# KickerBoard.net
KiCad netlist of a schematic drawn in EAGLE
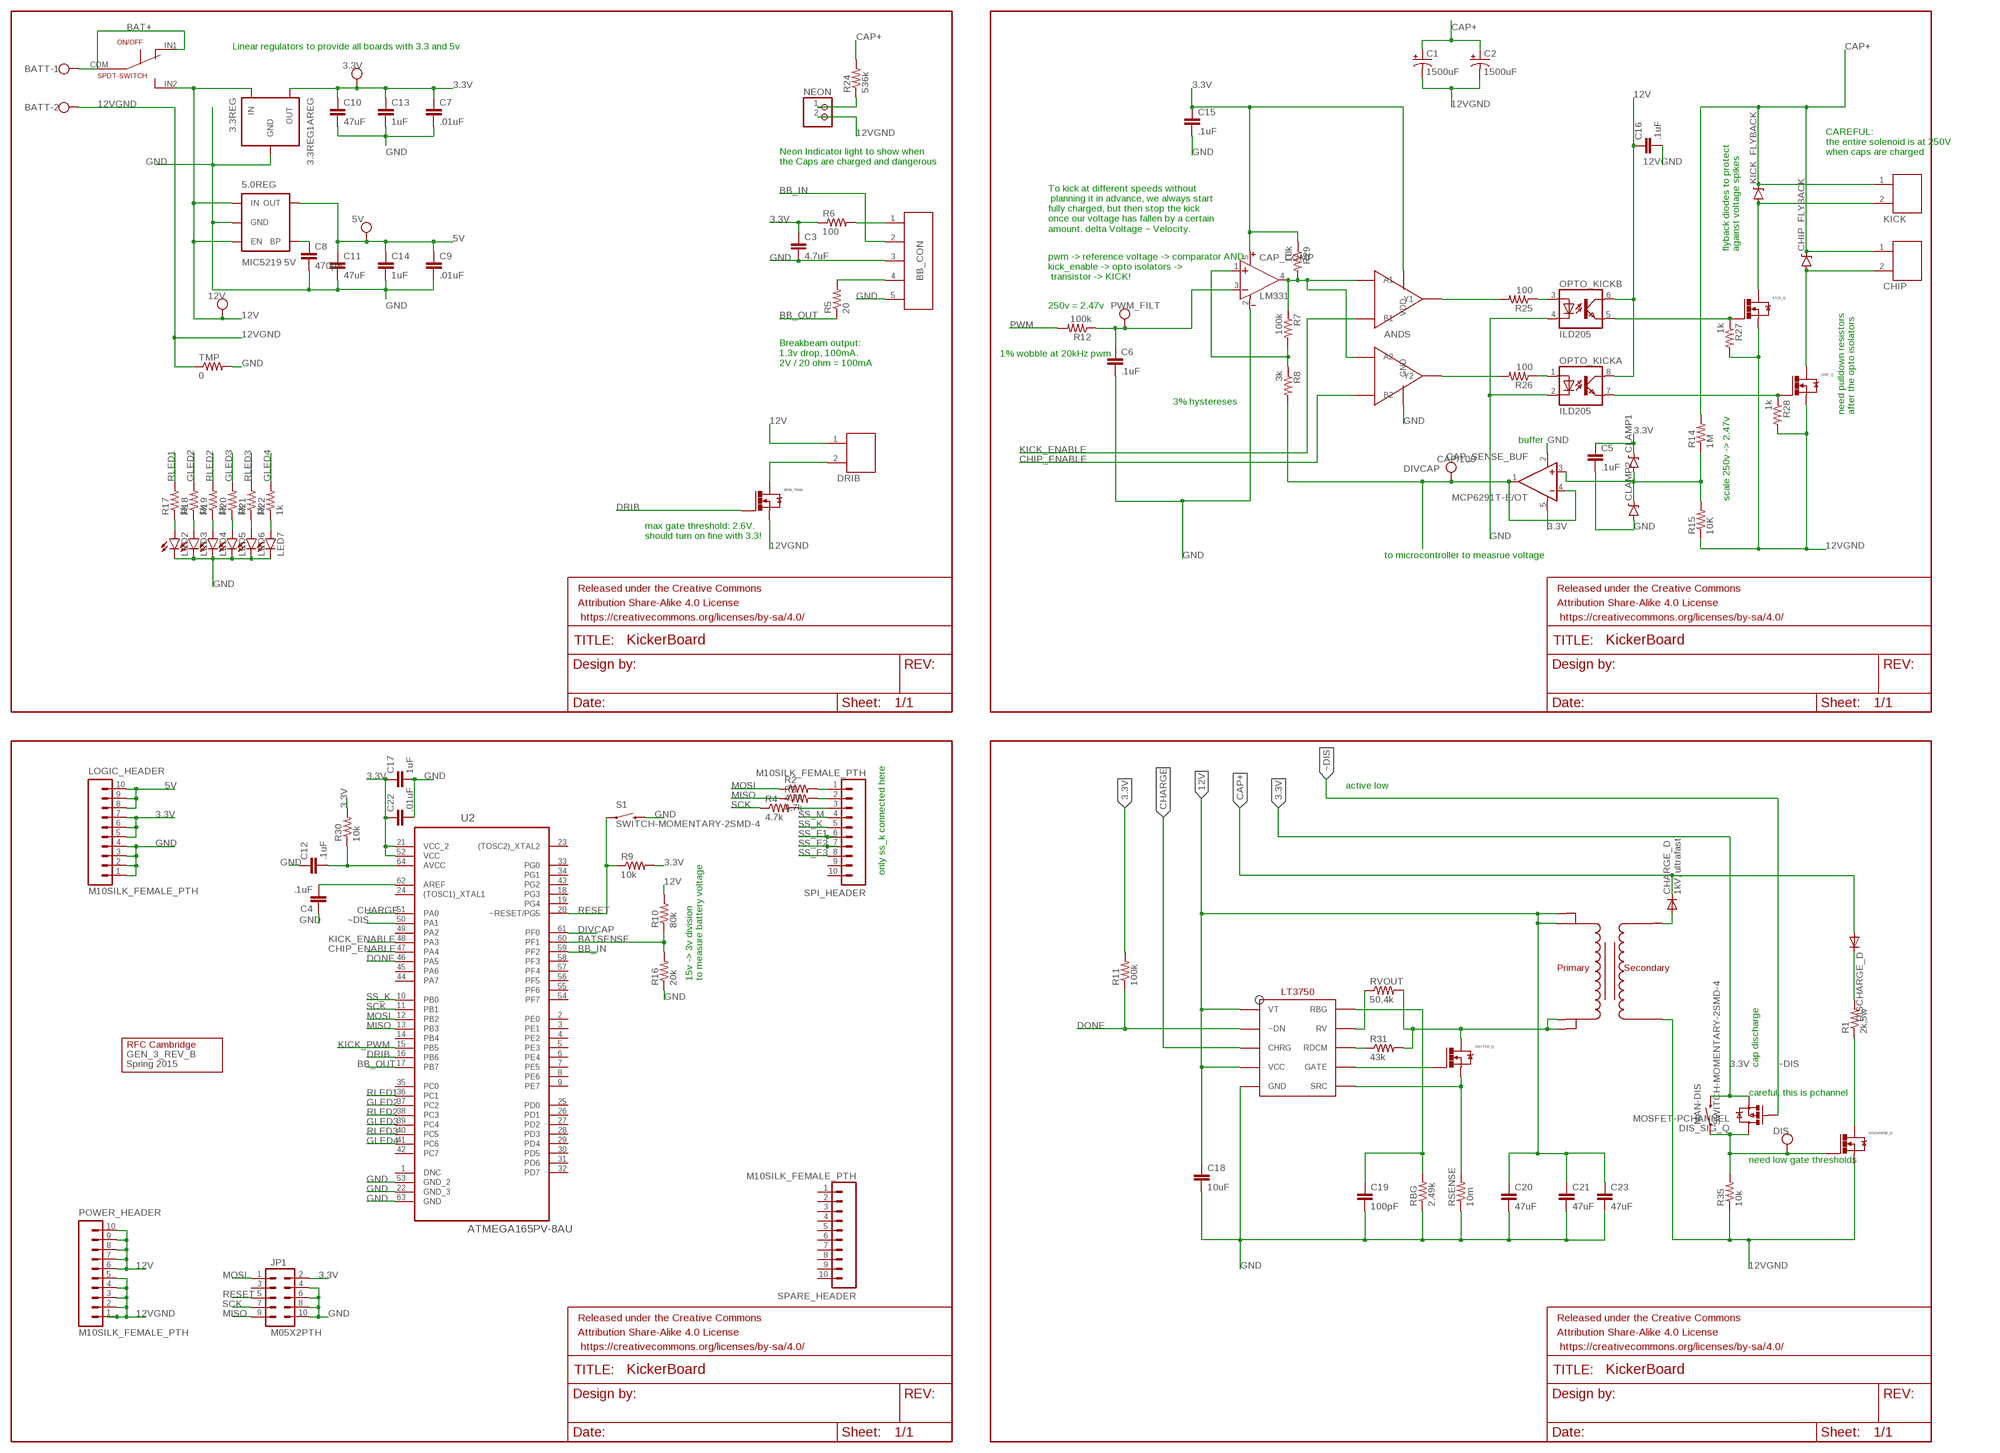
[diagram p0: schematic, sheet 1]

(export (version "E")
  (design (tool "Eeschema 10.0.6"))
  (components
    (comp (ref "3.3REG")
      (value "3.3REG1AREG")
      (footprint "eagle-import:DPAK")
      (libsource (lib "eagle-import") (part "3.3REG1AREG"))
    )
    (comp (ref "3.3V")
      (value "TEST_PT")
      (footprint "eagle-import:TESTING_PT")
      (libsource (lib "eagle-import") (part "TEST_PT"))
    )
    (comp (ref "5.0REG")
      (value "MIC5219 5V")
      (footprint "eagle-import:SOT23-5")
      (libsource (lib "eagle-import") (part "V_REG_MIC52195V"))
    )
    (comp (ref "5V")
      (value "TEST_PT")
      (footprint "eagle-import:TESTING_PT")
      (libsource (lib "eagle-import") (part "TEST_PT"))
    )
    (comp (ref "12V")
      (value "TEST_PT")
      (footprint "eagle-import:TESTING_PT")
      (libsource (lib "eagle-import") (part "TEST_PT"))
    )
    (comp (ref "ANDS")
      (value "AND-DUAL")
      (footprint "eagle-import:TSSOP8")
      (libsource (lib "eagle-import") (part "AND-DUAL"))
    )
    (comp (ref "BATT")
      (value "W237-102")
      (footprint "eagle-import:W237-102")
      (fields (field (name "MPN") "237-102"))
      (libsource (lib "eagle-import") (part "W237-102"))
    )
    (comp (ref "BB_CON")
      (value "JST-5")
      (footprint "eagle-import:JST-5-2MM")
      (libsource (lib "eagle-import") (part "JST-5"))
    )
    (comp (ref "C1")
      (value "1500uF")
      (footprint "eagle-import:EB35D")
      (libsource (lib "eagle-import") (part "CPOL-USE10-35"))
    )
    (comp (ref "C2")
      (value "1500uF")
      (footprint "eagle-import:EB35D")
      (libsource (lib "eagle-import") (part "CPOL-USE10-35"))
    )
    (comp (ref "C3")
      (value "4.7uF")
      (footprint "eagle-import:0805")
      (libsource (lib "eagle-import") (part "CAP0805"))
    )
    (comp (ref "C4")
      (value ".1uF")
      (footprint "eagle-import:0805")
      (libsource (lib "eagle-import") (part "CAP0805"))
    )
    (comp (ref "C5")
      (value ".1uF")
      (footprint "eagle-import:0805")
      (libsource (lib "eagle-import") (part "CAP0805"))
    )
    (comp (ref "C6")
      (value ".1uF")
      (footprint "eagle-import:0805")
      (libsource (lib "eagle-import") (part "CAP0805"))
    )
    (comp (ref "C7")
      (value ".01uF")
      (footprint "eagle-import:0805")
      (libsource (lib "eagle-import") (part "CAP0805"))
    )
    (comp (ref "C8")
      (value "470pF")
      (footprint "eagle-import:0805")
      (libsource (lib "eagle-import") (part "CAP0805"))
    )
    (comp (ref "C9")
      (value ".01uF")
      (footprint "eagle-import:0805")
      (libsource (lib "eagle-import") (part "CAP0805"))
    )
    (comp (ref "C10")
      (value "47uF")
      (footprint "eagle-import:1206")
      (libsource (lib "eagle-import") (part "CAP1206"))
    )
    (comp (ref "C11")
      (value "47uF")
      (footprint "eagle-import:1206")
      (libsource (lib "eagle-import") (part "CAP1206"))
    )
    (comp (ref "C12")
      (value ".1uF")
      (footprint "eagle-import:0805")
      (libsource (lib "eagle-import") (part "CAP0805"))
    )
    (comp (ref "C13")
      (value "1uF")
      (footprint "eagle-import:0805")
      (libsource (lib "eagle-import") (part "CAP0805"))
    )
    (comp (ref "C14")
      (value "1uF")
      (footprint "eagle-import:0805")
      (libsource (lib "eagle-import") (part "CAP0805"))
    )
    (comp (ref "C15")
      (value ".1uF")
      (footprint "eagle-import:0805")
      (libsource (lib "eagle-import") (part "CAP0805"))
    )
    (comp (ref "C16")
      (value ".1uF")
      (footprint "eagle-import:0805")
      (libsource (lib "eagle-import") (part "CAP0805"))
    )
    (comp (ref "C17")
      (value "1uF")
      (footprint "eagle-import:0805")
      (libsource (lib "eagle-import") (part "CAP0805"))
    )
    (comp (ref "C18")
      (value "10uF")
      (footprint "eagle-import:0805")
      (libsource (lib "eagle-import") (part "CAP0805"))
    )
    (comp (ref "C19")
      (value "100pF")
      (footprint "eagle-import:0805")
      (libsource (lib "eagle-import") (part "CAP0805"))
    )
    (comp (ref "C20")
      (value "47uF")
      (footprint "eagle-import:1206")
      (libsource (lib "eagle-import") (part "CAP1206"))
    )
    (comp (ref "C21")
      (value "47uF")
      (footprint "eagle-import:1206")
      (libsource (lib "eagle-import") (part "CAP1206"))
    )
    (comp (ref "C22")
      (value ".01uF")
      (footprint "eagle-import:0805")
      (libsource (lib "eagle-import") (part "CAP0805"))
    )
    (comp (ref "C23")
      (value "47uF")
      (footprint "eagle-import:1206")
      (libsource (lib "eagle-import") (part "CAP1206"))
    )
    (comp (ref "CAP/100")
      (value "TEST_PT")
      (footprint "eagle-import:TESTING_PT")
      (libsource (lib "eagle-import") (part "TEST_PT"))
    )
    (comp (ref "CAP_COMP")
      (value "LM331")
      (footprint "eagle-import:SOT23-5")
      (libsource (lib "eagle-import") (part "LM331"))
    )
    (comp (ref "CAP_SENSE_BUF")
      (value "MCP6291T-E/OT")
      (footprint "eagle-import:SOT23-5")
      (libsource (lib "eagle-import") (part "MCP6291T-E/OT"))
    )
    (comp (ref "CHARGE_D")
      (value "1kV, ultrafast")
      (footprint "eagle-import:DO214AC")
      (libsource (lib "eagle-import") (part "DIODE-DO214AC"))
    )
    (comp (ref "CHARGE_U")
      (value "LT3750")
      (footprint "eagle-import:10-MSOP")
      (libsource (lib "eagle-import") (part "LT3750"))
    )
    (comp (ref "CHIP")
      (value "JST-22MM")
      (footprint "eagle-import:JST-2-2MM")
      (libsource (lib "eagle-import") (part "JST-22MM"))
    )
    (comp (ref "CHIP_FLYBACK")
      (value "DIODE-ZENERDO214AB")
      (footprint "eagle-import:DO214AB")
      (libsource (lib "eagle-import") (part "DIODE-ZENERDO214AB"))
    )
    (comp (ref "CHIP_Q")
      (value "N-MOSFETDPAK")
      (footprint "eagle-import:DPAK")
      (libsource (lib "eagle-import") (part "N-MOSFETDPAK"))
    )
    (comp (ref "CLAMP1")
      (value "DIODE-ZENERDO214AC")
      (footprint "eagle-import:DO214AC")
      (libsource (lib "eagle-import") (part "DIODE-ZENERDO214AC"))
    )
    (comp (ref "CLAMP2")
      (value "DIODE-ZENERDO214AC")
      (footprint "eagle-import:DO214AC")
      (libsource (lib "eagle-import") (part "DIODE-ZENERDO214AC"))
    )
    (comp (ref "DIS")
      (value "TEST_PT")
      (footprint "eagle-import:TESTING_PT")
      (libsource (lib "eagle-import") (part "TEST_PT"))
    )
    (comp (ref "DISCHARGE_D")
      (value "DIODE-DO214AA")
      (footprint "eagle-import:DO214AA")
      (libsource (lib "eagle-import") (part "DIODE-DO214AA"))
    )
    (comp (ref "DISCHARGE_Q")
      (value "N-MOSFETDPAK")
      (footprint "eagle-import:DPAK")
      (libsource (lib "eagle-import") (part "N-MOSFETDPAK"))
    )
    (comp (ref "DIS_SIG_Q")
      (value "MOSFET-PCHANNEL")
      (footprint "eagle-import:SOT23-3")
      (libsource (lib "eagle-import") (part "MOSFET-PCHANNEL"))
    )
    (comp (ref "DRIB")
      (value "JST-22MM")
      (footprint "eagle-import:JST-2-2MM")
      (libsource (lib "eagle-import") (part "JST-22MM"))
    )
    (comp (ref "DRIB_TRAN")
      (value "N-MOSFETDPAK")
      (footprint "eagle-import:DPAK")
      (libsource (lib "eagle-import") (part "N-MOSFETDPAK"))
    )
    (comp (ref "FRAME1")
      (value "FRAME-LETTER")
      (footprint "eagle-import:CREATIVE_COMMONS")
      (libsource (lib "eagle-import") (part "FRAME-LETTER"))
    )
    (comp (ref "FRAME2")
      (value "FRAME-LETTER")
      (footprint "eagle-import:CREATIVE_COMMONS")
      (libsource (lib "eagle-import") (part "FRAME-LETTER"))
    )
    (comp (ref "FRAME3")
      (value "FRAME-LETTER")
      (footprint "eagle-import:CREATIVE_COMMONS")
      (libsource (lib "eagle-import") (part "FRAME-LETTER"))
    )
    (comp (ref "FRAME4")
      (value "FRAME-LETTER")
      (footprint "eagle-import:CREATIVE_COMMONS")
      (libsource (lib "eagle-import") (part "FRAME-LETTER"))
    )
    (comp (ref "GEN_3_REV_B")
      (value "Spring 2015")
      (footprint "eagle-import:LOGO")
      (libsource (lib "eagle-import") (part "LOGO"))
    )
    (comp (ref "JP1")
      (value "M05X2PTH")
      (footprint "eagle-import:AVR_ICSP")
      (libsource (lib "eagle-import") (part "M05X2PTH"))
    )
    (comp (ref "KICK")
      (value "JST-22MM")
      (footprint "eagle-import:JST-2-2MM")
      (libsource (lib "eagle-import") (part "JST-22MM"))
    )
    (comp (ref "KICK_FLYBACK")
      (value "DIODE-ZENERDO214AB")
      (footprint "eagle-import:DO214AB")
      (libsource (lib "eagle-import") (part "DIODE-ZENERDO214AB"))
    )
    (comp (ref "KICK_Q")
      (value "N-MOSFETDPAK")
      (footprint "eagle-import:DPAK")
      (libsource (lib "eagle-import") (part "N-MOSFETDPAK"))
    )
    (comp (ref "LED2")
      (value "LED1206")
      (footprint "eagle-import:LED-1206")
      (libsource (lib "eagle-import") (part "LED1206"))
    )
    (comp (ref "LED3")
      (value "LED1206")
      (footprint "eagle-import:LED-1206")
      (libsource (lib "eagle-import") (part "LED1206"))
    )
    (comp (ref "LED4")
      (value "LED1206")
      (footprint "eagle-import:LED-1206")
      (libsource (lib "eagle-import") (part "LED1206"))
    )
    (comp (ref "LED5")
      (value "LED1206")
      (footprint "eagle-import:LED-1206")
      (libsource (lib "eagle-import") (part "LED1206"))
    )
    (comp (ref "LED6")
      (value "LED1206")
      (footprint "eagle-import:LED-1206")
      (libsource (lib "eagle-import") (part "LED1206"))
    )
    (comp (ref "LED7")
      (value "LED1206")
      (footprint "eagle-import:LED-1206")
      (libsource (lib "eagle-import") (part "LED1206"))
    )
    (comp (ref "LOGIC_HEADER")
      (value "M10SILK_FEMALE_PTH")
      (footprint "eagle-import:1X10")
      (libsource (lib "eagle-import") (part "M10SILK_FEMALE_PTH"))
    )
    (comp (ref "MAN-DIS")
      (value "SWITCH-MOMENTARY-2SMD-4")
      (footprint "eagle-import:TACTILE_SWITCH_TALL")
      (libsource (lib "eagle-import") (part "SWITCH-MOMENTARY-2SMD-4"))
    )
    (comp (ref "NEON")
      (value "PINHD-1X2")
      (footprint "eagle-import:1X02")
      (libsource (lib "eagle-import") (part "PINHD-1X2"))
    )
    (comp (ref "ON/OFF")
      (value "SPDT-SWITCH")
      (footprint "eagle-import:CK_SWITCH")
      (libsource (lib "eagle-import") (part "SPDT-SWITCH"))
    )
    (comp (ref "OPTO_KICK")
      (value "ILD205")
      (footprint "eagle-import:SOIC08")
      (fields (field (name "MF") "VISHAY/TELEFUNKEN") (field (name "MPN") "ILD205T"))
      (libsource (lib "eagle-import") (part "ILD205"))
    )
    (comp (ref "POWER_HEADER")
      (value "M10SILK_FEMALE_PTH")
      (footprint "eagle-import:1X10")
      (libsource (lib "eagle-import") (part "M10SILK_FEMALE_PTH"))
    )
    (comp (ref "PWM_FILT")
      (value "TEST_PT")
      (footprint "eagle-import:TESTING_PT")
      (libsource (lib "eagle-import") (part "TEST_PT"))
    )
    (comp (ref "R1")
      (value "2k,5w")
      (footprint "eagle-import:5WRESISTOR")
      (libsource (lib "eagle-import") (part "RESISTOR"))
    )
    (comp (ref "R2")
      (value "4.7k")
      (footprint "eagle-import:0805")
      (libsource (lib "eagle-import") (part "RESISTOR0805-RES"))
    )
    (comp (ref "R3")
      (value "4.7k")
      (footprint "eagle-import:0805")
      (libsource (lib "eagle-import") (part "RESISTOR0805-RES"))
    )
    (comp (ref "R4")
      (value "4.7k")
      (footprint "eagle-import:0805")
      (libsource (lib "eagle-import") (part "RESISTOR0805-RES"))
    )
    (comp (ref "R5")
      (value "20")
      (footprint "eagle-import:0805")
      (libsource (lib "eagle-import") (part "RESISTOR0805-RES"))
    )
    (comp (ref "R6")
      (value "100")
      (footprint "eagle-import:0805")
      (libsource (lib "eagle-import") (part "RESISTOR0805-RES"))
    )
    (comp (ref "R7")
      (value "100k")
      (footprint "eagle-import:0805")
      (libsource (lib "eagle-import") (part "RESISTOR0805-RES"))
    )
    (comp (ref "R8")
      (value "3k")
      (footprint "eagle-import:0805")
      (libsource (lib "eagle-import") (part "RESISTOR0805-RES"))
    )
    (comp (ref "R9")
      (value "10k")
      (footprint "eagle-import:0805")
      (libsource (lib "eagle-import") (part "RESISTOR0805-RES"))
    )
    (comp (ref "R10")
      (value "80k")
      (footprint "eagle-import:0805")
      (libsource (lib "eagle-import") (part "RESISTOR0805-RES"))
    )
    (comp (ref "R11")
      (value "100k")
      (footprint "eagle-import:0805")
      (libsource (lib "eagle-import") (part "RESISTOR0805-RES"))
    )
    (comp (ref "R12")
      (value "100k")
      (footprint "eagle-import:0805")
      (libsource (lib "eagle-import") (part "RESISTOR0805-RES"))
    )
    (comp (ref "R14")
      (value "1M")
      (footprint "eagle-import:0805")
      (libsource (lib "eagle-import") (part "SparkFun-Resistors_RESISTOR0805-RES"))
    )
    (comp (ref "R15")
      (value "10K")
      (footprint "eagle-import:0805")
      (libsource (lib "eagle-import") (part "SparkFun-Resistors_RESISTOR0805-RES"))
    )
    (comp (ref "R16")
      (value "20k")
      (footprint "eagle-import:0805")
      (libsource (lib "eagle-import") (part "RESISTOR0805-RES"))
    )
    (comp (ref "R17")
      (value "1k")
      (footprint "eagle-import:0805")
      (libsource (lib "eagle-import") (part "RESISTOR0805-RES"))
    )
    (comp (ref "R18")
      (value "1k")
      (footprint "eagle-import:0805")
      (libsource (lib "eagle-import") (part "RESISTOR0805-RES"))
    )
    (comp (ref "R19")
      (value "1k")
      (footprint "eagle-import:0805")
      (libsource (lib "eagle-import") (part "RESISTOR0805-RES"))
    )
    (comp (ref "R20")
      (value "1k")
      (footprint "eagle-import:0805")
      (libsource (lib "eagle-import") (part "RESISTOR0805-RES"))
    )
    (comp (ref "R21")
      (value "1k")
      (footprint "eagle-import:0805")
      (libsource (lib "eagle-import") (part "RESISTOR0805-RES"))
    )
    (comp (ref "R22")
      (value "1k")
      (footprint "eagle-import:0805")
      (libsource (lib "eagle-import") (part "RESISTOR0805-RES"))
    )
    (comp (ref "R24")
      (value "536k")
      (footprint "eagle-import:0805")
      (libsource (lib "eagle-import") (part "RESISTOR0805-RES"))
    )
    (comp (ref "R25")
      (value "100")
      (footprint "eagle-import:0805")
      (libsource (lib "eagle-import") (part "RESISTOR0805-RES"))
    )
    (comp (ref "R26")
      (value "100")
      (footprint "eagle-import:0805")
      (libsource (lib "eagle-import") (part "RESISTOR0805-RES"))
    )
    (comp (ref "R27")
      (value "1k")
      (footprint "eagle-import:0805")
      (libsource (lib "eagle-import") (part "RESISTOR0805-RES"))
    )
    (comp (ref "R28")
      (value "1k")
      (footprint "eagle-import:0805")
      (libsource (lib "eagle-import") (part "RESISTOR0805-RES"))
    )
    (comp (ref "R29")
      (value "10k")
      (footprint "eagle-import:0805")
      (libsource (lib "eagle-import") (part "RESISTOR0805-RES"))
    )
    (comp (ref "R30")
      (value "10k")
      (footprint "eagle-import:0805")
      (libsource (lib "eagle-import") (part "RESISTOR0805-RES"))
    )
    (comp (ref "R31")
      (value "43k")
      (footprint "eagle-import:0805")
      (libsource (lib "eagle-import") (part "RESISTOR0805-RES"))
    )
    (comp (ref "R35")
      (value "10k")
      (footprint "eagle-import:0805")
      (libsource (lib "eagle-import") (part "RESISTOR0805-RES"))
    )
    (comp (ref "RBG")
      (value "2.49k")
      (footprint "eagle-import:0805")
      (libsource (lib "eagle-import") (part "RESISTOR0805-RES"))
    )
    (comp (ref "RSENSE")
      (value "10m")
      (footprint "eagle-import:R2512")
      (libsource (lib "eagle-import") (part "RESISTOR2512"))
    )
    (comp (ref "RVOUT")
      (value "50.4k")
      (footprint "eagle-import:0805")
      (libsource (lib "eagle-import") (part "RESISTOR0805-RES"))
    )
    (comp (ref "S1")
      (value "SWITCH-MOMENTARY-2SMD-4")
      (footprint "eagle-import:TACTILE_SWITCH_TALL")
      (libsource (lib "eagle-import") (part "SWITCH-MOMENTARY-2SMD-4"))
    )
    (comp (ref "SPARE_HEADER")
      (value "M10SILK_FEMALE_PTH")
      (footprint "eagle-import:1X10")
      (libsource (lib "eagle-import") (part "M10SILK_FEMALE_PTH"))
    )
    (comp (ref "SPI_HEADER")
      (value "M10SILK_FEMALE_PTH")
      (footprint "eagle-import:1X10")
      (libsource (lib "eagle-import") (part "M10SILK_FEMALE_PTH"))
    )
    (comp (ref "SWITCH_Q")
      (value "N-MOSFETDPAK")
      (footprint "eagle-import:DPAK")
      (libsource (lib "eagle-import") (part "N-MOSFETDPAK"))
    )
    (comp (ref "TMP")
      (value "0")
      (footprint "eagle-import:0805")
      (libsource (lib "eagle-import") (part "RESISTOR0805-RES"))
    )
    (comp (ref "U$1")
      (value "32052-TRANSFORMER")
      (footprint "eagle-import:10-TRANSFORMER")
      (libsource (lib "eagle-import") (part "32052-TRANSFORMER"))
    )
    (comp (ref "U2")
      (value "ATMEGA165PV-8AU")
      (footprint "eagle-import:QFP80P1600X1600X120-64N")
      (libsource (lib "eagle-import") (part "ATMEGA165PV-8AU"))
    )
  )
  (nets
    (net (code "1") (name "/5V") (class "Default")
      (node (ref "5.0REG") (pin "5") (pinfunction "OUT_5") (pintype "passive"))
      (node (ref "5V") (pin "P$1") (pinfunction "P$1_P$1") (pintype "bidirectional"))
      (node (ref "C11") (pin "1") (pinfunction "1_1") (pintype "passive"))
      (node (ref "C14") (pin "1") (pinfunction "1_1") (pintype "passive"))
      (node (ref "C9") (pin "1") (pinfunction "1_1") (pintype "passive"))
      (node (ref "LOGIC_HEADER") (pin "10") (pinfunction "10_10") (pintype "passive"))
      (node (ref "LOGIC_HEADER") (pin "8") (pinfunction "8_8") (pintype "passive"))
      (node (ref "LOGIC_HEADER") (pin "9") (pinfunction "9_9") (pintype "passive"))
    )
    (net (code "2") (name "/12VGND") (class "Default")
      (node (ref "BATT") (pin "2") (pinfunction "KL_2") (pintype "passive"))
      (node (ref "C1") (pin "-") (pinfunction "-_-") (pintype "passive"))
      (node (ref "C16") (pin "2") (pinfunction "2_2") (pintype "passive"))
      (node (ref "C2") (pin "-") (pinfunction "-_-") (pintype "passive"))
      (node (ref "CHIP_Q") (pin "SOURCE") (pinfunction "S_SOURCE") (pintype "bidirectional"))
      (node (ref "DISCHARGE_Q") (pin "SOURCE") (pinfunction "S_SOURCE") (pintype "bidirectional"))
      (node (ref "DRIB_TRAN") (pin "SOURCE") (pinfunction "S_SOURCE") (pintype "bidirectional"))
      (node (ref "KICK_Q") (pin "SOURCE") (pinfunction "S_SOURCE") (pintype "bidirectional"))
      (node (ref "NEON") (pin "2") (pinfunction "2_2") (pintype "passive"))
      (node (ref "POWER_HEADER") (pin "1") (pinfunction "1_1") (pintype "passive"))
      (node (ref "POWER_HEADER") (pin "2") (pinfunction "2_2") (pintype "passive"))
      (node (ref "POWER_HEADER") (pin "3") (pinfunction "3_3") (pintype "passive"))
      (node (ref "POWER_HEADER") (pin "4") (pinfunction "4_4") (pintype "passive"))
      (node (ref "POWER_HEADER") (pin "5") (pinfunction "5_5") (pintype "passive"))
      (node (ref "R15") (pin "1") (pinfunction "1_1") (pintype "passive"))
      (node (ref "R27") (pin "2") (pinfunction "2_2") (pintype "passive"))
      (node (ref "R28") (pin "2") (pinfunction "2_2") (pintype "passive"))
      (node (ref "R35") (pin "1") (pinfunction "1_1") (pintype "passive"))
      (node (ref "TMP") (pin "1") (pinfunction "1_1") (pintype "passive"))
      (node (ref "U$1") (pin "P$10") (pinfunction "P$10_P$10") (pintype "bidirectional"))
    )
    (net (code "3") (name "/BAT+") (class "Default")
      (node (ref "BATT") (pin "1") (pinfunction "KL_1") (pintype "passive"))
      (node (ref "ON/OFF") (pin "COM") (pinfunction "COM_COM") (pintype "bidirectional"))
      (node (ref "ON/OFF") (pin "IN1") (pinfunction "P1_IN1") (pintype "bidirectional"))
    )
    (net (code "4") (name "/BATSENSE") (class "Default")
      (node (ref "R10") (pin "1") (pinfunction "1_1") (pintype "passive"))
      (node (ref "R16") (pin "2") (pinfunction "2_2") (pintype "passive"))
      (node (ref "U2") (pin "60") (pinfunction "PF1_60") (pintype "bidirectional"))
    )
    (net (code "5") (name "/BB_IN") (class "Default")
      (node (ref "BB_CON") (pin "2") (pinfunction "P$2_2") (pintype "bidirectional"))
      (node (ref "U2") (pin "59") (pinfunction "PF2_59") (pintype "bidirectional"))
    )
    (net (code "6") (name "/BB_OUT") (class "Default")
      (node (ref "R5") (pin "1") (pinfunction "1_1") (pintype "passive"))
      (node (ref "U2") (pin "17") (pinfunction "PB7_17") (pintype "bidirectional"))
    )
    (net (code "7") (name "/CHIP_ENABLE") (class "Default")
      (node (ref "ANDS") (pin "P$6") (pinfunction "B2_P$6") (pintype "bidirectional"))
      (node (ref "U2") (pin "47") (pinfunction "PA4_47") (pintype "bidirectional"))
    )
    (net (code "8") (name "/DIVCAP") (class "Default")
      (node (ref "CAP/100") (pin "P$1") (pinfunction "P$1_P$1") (pintype "bidirectional"))
      (node (ref "CAP_SENSE_BUF") (pin "1") (pinfunction "OUT_1") (pintype "output"))
      (node (ref "CAP_SENSE_BUF") (pin "4") (pinfunction "-IN_4") (pintype "input"))
      (node (ref "R8") (pin "2") (pinfunction "2_2") (pintype "passive"))
      (node (ref "U2") (pin "61") (pinfunction "PF0_61") (pintype "bidirectional"))
    )
    (net (code "9") (name "/DONE") (class "Default")
      (node (ref "CHARGE_U") (pin "P$2") (pinfunction "~{DN}_P$2") (pintype "bidirectional"))
      (node (ref "R11") (pin "1") (pinfunction "1_1") (pintype "passive"))
      (node (ref "U2") (pin "46") (pinfunction "PA5_46") (pintype "bidirectional"))
    )
    (net (code "10") (name "/DRIB") (class "Default")
      (node (ref "DRIB_TRAN") (pin "GATE") (pinfunction "G_GATE") (pintype "bidirectional"))
      (node (ref "U2") (pin "16") (pinfunction "PB6_16") (pintype "bidirectional"))
    )
    (net (code "11") (name "/GLED2") (class "Default")
      (node (ref "R18") (pin "2") (pinfunction "2_2") (pintype "passive"))
      (node (ref "U2") (pin "37") (pinfunction "PC2_37") (pintype "bidirectional"))
    )
    (net (code "12") (name "/GLED3") (class "Default")
      (node (ref "R20") (pin "2") (pinfunction "2_2") (pintype "passive"))
      (node (ref "U2") (pin "39") (pinfunction "PC4_39") (pintype "bidirectional"))
    )
    (net (code "13") (name "/GLED4") (class "Default")
      (node (ref "R22") (pin "2") (pinfunction "2_2") (pintype "passive"))
      (node (ref "U2") (pin "41") (pinfunction "PC6_41") (pintype "bidirectional"))
    )
    (net (code "14") (name "/GND") (class "Default")
      (node (ref "3.3REG") (pin "DRAIN") (pinfunction "GND_DRAIN") (pintype "bidirectional"))
      (node (ref "5.0REG") (pin "2") (pinfunction "GND_2") (pintype "input"))
      (node (ref "ANDS") (pin "P$4") (pinfunction "GND_P$4") (pintype "bidirectional"))
      (node (ref "BB_CON") (pin "3") (pinfunction "P$3_3") (pintype "bidirectional"))
      (node (ref "BB_CON") (pin "5") (pinfunction "P$5_5") (pintype "bidirectional"))
      (node (ref "C10") (pin "2") (pinfunction "2_2") (pintype "passive"))
      (node (ref "C11") (pin "2") (pinfunction "2_2") (pintype "passive"))
      (node (ref "C12") (pin "1") (pinfunction "1_1") (pintype "passive"))
      (node (ref "C13") (pin "2") (pinfunction "2_2") (pintype "passive"))
      (node (ref "C14") (pin "2") (pinfunction "2_2") (pintype "passive"))
      (node (ref "C15") (pin "2") (pinfunction "2_2") (pintype "passive"))
      (node (ref "C17") (pin "2") (pinfunction "2_2") (pintype "passive"))
      (node (ref "C18") (pin "2") (pinfunction "2_2") (pintype "passive"))
      (node (ref "C19") (pin "2") (pinfunction "2_2") (pintype "passive"))
      (node (ref "C20") (pin "2") (pinfunction "2_2") (pintype "passive"))
      (node (ref "C21") (pin "2") (pinfunction "2_2") (pintype "passive"))
      (node (ref "C22") (pin "2") (pinfunction "2_2") (pintype "passive"))
      (node (ref "C23") (pin "2") (pinfunction "2_2") (pintype "passive"))
      (node (ref "C3") (pin "2") (pinfunction "2_2") (pintype "passive"))
      (node (ref "C4") (pin "1") (pinfunction "1_1") (pintype "passive"))
      (node (ref "C5") (pin "2") (pinfunction "2_2") (pintype "passive"))
      (node (ref "C6") (pin "2") (pinfunction "2_2") (pintype "passive"))
      (node (ref "C7") (pin "2") (pinfunction "2_2") (pintype "passive"))
      (node (ref "C8") (pin "2") (pinfunction "2_2") (pintype "passive"))
      (node (ref "C9") (pin "2") (pinfunction "2_2") (pintype "passive"))
      (node (ref "CAP_COMP") (pin "2") (pinfunction "V-_2") (pintype "power_in"))
      (node (ref "CAP_SENSE_BUF") (pin "2") (pinfunction "V-_2") (pintype "power_in"))
      (node (ref "CHARGE_U") (pin "P$5") (pinfunction "GND_P$5") (pintype "bidirectional"))
      (node (ref "CLAMP2") (pin "A") (pinfunction "A_A") (pintype "passive"))
      (node (ref "JP1") (pin "10") (pinfunction "10_10") (pintype "passive"))
      (node (ref "JP1") (pin "4") (pinfunction "4_4") (pintype "passive"))
      (node (ref "JP1") (pin "6") (pinfunction "6_6") (pintype "passive"))
      (node (ref "JP1") (pin "8") (pinfunction "8_8") (pintype "passive"))
      (node (ref "LED2") (pin "C") (pinfunction "C_C") (pintype "passive"))
      (node (ref "LED3") (pin "C") (pinfunction "C_C") (pintype "passive"))
      (node (ref "LED4") (pin "C") (pinfunction "C_C") (pintype "passive"))
      (node (ref "LED5") (pin "C") (pinfunction "C_C") (pintype "passive"))
      (node (ref "LED6") (pin "C") (pinfunction "C_C") (pintype "passive"))
      (node (ref "LED7") (pin "C") (pinfunction "C_C") (pintype "passive"))
      (node (ref "LOGIC_HEADER") (pin "1") (pinfunction "1_1") (pintype "passive"))
      (node (ref "LOGIC_HEADER") (pin "2") (pinfunction "2_2") (pintype "passive"))
      (node (ref "LOGIC_HEADER") (pin "3") (pinfunction "3_3") (pintype "passive"))
      (node (ref "LOGIC_HEADER") (pin "4") (pinfunction "4_4") (pintype "passive"))
      (node (ref "OPTO_KICK") (pin "2") (pinfunction "C_2") (pintype "passive"))
      (node (ref "OPTO_KICK") (pin "4") (pinfunction "C_4") (pintype "passive"))
      (node (ref "R16") (pin "1") (pinfunction "1_1") (pintype "passive"))
      (node (ref "RBG") (pin "1") (pinfunction "1_1") (pintype "passive"))
      (node (ref "RSENSE") (pin "1") (pinfunction "1_1") (pintype "passive"))
      (node (ref "S1") (pin "B2") (pinfunction "2_B2") (pintype "passive"))
      (node (ref "TMP") (pin "2") (pinfunction "2_2") (pintype "passive"))
      (node (ref "U2") (pin "22") (pinfunction "GND_3_22") (pintype "passive"))
      (node (ref "U2") (pin "53") (pinfunction "GND_2_53") (pintype "passive"))
      (node (ref "U2") (pin "63") (pinfunction "GND_63") (pintype "passive"))
    )
    (net (code "15") (name "/KICK_ENABLE") (class "Default")
      (node (ref "ANDS") (pin "P$2") (pinfunction "B1_P$2") (pintype "bidirectional"))
      (node (ref "U2") (pin "48") (pinfunction "PA3_48") (pintype "bidirectional"))
    )
    (net (code "16") (name "/KICK_PWM") (class "Default")
      (node (ref "U2") (pin "15") (pinfunction "PB5_15") (pintype "bidirectional"))
    )
    (net (code "17") (name "/MISO") (class "Default")
      (node (ref "JP1") (pin "9") (pinfunction "9_9") (pintype "passive"))
      (node (ref "R3") (pin "1") (pinfunction "1_1") (pintype "passive"))
      (node (ref "U2") (pin "13") (pinfunction "PB3_13") (pintype "bidirectional"))
    )
    (net (code "18") (name "/MOSI") (class "Default")
      (node (ref "JP1") (pin "1") (pinfunction "1_1") (pintype "passive"))
      (node (ref "R2") (pin "1") (pinfunction "1_1") (pintype "passive"))
      (node (ref "U2") (pin "12") (pinfunction "PB2_12") (pintype "bidirectional"))
    )
    (net (code "19") (name "/PWM") (class "Default")
      (node (ref "R12") (pin "2") (pinfunction "2_2") (pintype "passive"))
    )
    (net (code "20") (name "/RESET") (class "Default")
      (node (ref "JP1") (pin "5") (pinfunction "5_5") (pintype "passive"))
      (node (ref "R9") (pin "1") (pinfunction "1_1") (pintype "passive"))
      (node (ref "S1") (pin "A2") (pinfunction "1_A2") (pintype "passive"))
      (node (ref "U2") (pin "20") (pinfunction "~{RESET/PG5}_20") (pintype "bidirectional"))
    )
    (net (code "21") (name "/RLED1") (class "Default")
      (node (ref "R17") (pin "2") (pinfunction "2_2") (pintype "passive"))
      (node (ref "U2") (pin "36") (pinfunction "PC1_36") (pintype "bidirectional"))
    )
    (net (code "22") (name "/RLED2") (class "Default")
      (node (ref "R19") (pin "2") (pinfunction "2_2") (pintype "passive"))
      (node (ref "U2") (pin "38") (pinfunction "PC3_38") (pintype "bidirectional"))
    )
    (net (code "23") (name "/RLED3") (class "Default")
      (node (ref "R21") (pin "2") (pinfunction "2_2") (pintype "passive"))
      (node (ref "U2") (pin "40") (pinfunction "PC5_40") (pintype "bidirectional"))
    )
    (net (code "24") (name "/SCK") (class "Default")
      (node (ref "JP1") (pin "7") (pinfunction "7_7") (pintype "passive"))
      (node (ref "R4") (pin "1") (pinfunction "1_1") (pintype "passive"))
      (node (ref "U2") (pin "11") (pinfunction "PB1_11") (pintype "bidirectional"))
    )
    (net (code "25") (name "/SS_E1") (class "Default")
      (node (ref "SPI_HEADER") (pin "6") (pinfunction "6_6") (pintype "passive"))
    )
    (net (code "26") (name "/SS_E2") (class "Default")
      (node (ref "SPI_HEADER") (pin "7") (pinfunction "7_7") (pintype "passive"))
    )
    (net (code "27") (name "/SS_E3") (class "Default")
      (node (ref "SPI_HEADER") (pin "8") (pinfunction "8_8") (pintype "passive"))
    )
    (net (code "28") (name "/SS_K") (class "Default")
      (node (ref "SPI_HEADER") (pin "5") (pinfunction "5_5") (pintype "passive"))
      (node (ref "U2") (pin "10") (pinfunction "PB0_10") (pintype "bidirectional"))
    )
    (net (code "29") (name "/SS_M") (class "Default")
      (node (ref "SPI_HEADER") (pin "4") (pinfunction "4_4") (pintype "passive"))
    )
    (net (code "30") (name "/~{DIS}") (class "Default")
      (node (ref "DIS_SIG_Q") (pin "1") (pinfunction "G_1") (pintype "passive"))
      (node (ref "U2") (pin "50") (pinfunction "PA1_50") (pintype "bidirectional"))
    )
    (net (code "31") (name "3.3V") (class "Default")
      (node (ref "3.3REG") (pin "SOURCE") (pinfunction "OUT_SOURCE") (pintype "bidirectional"))
      (node (ref "3.3V") (pin "P$1") (pinfunction "P$1_P$1") (pintype "bidirectional"))
      (node (ref "ANDS") (pin "P$8") (pinfunction "VDD_P$8") (pintype "bidirectional"))
      (node (ref "C10") (pin "1") (pinfunction "1_1") (pintype "passive"))
      (node (ref "C13") (pin "1") (pinfunction "1_1") (pintype "passive"))
      (node (ref "C15") (pin "1") (pinfunction "1_1") (pintype "passive"))
      (node (ref "C17") (pin "1") (pinfunction "1_1") (pintype "passive"))
      (node (ref "C22") (pin "1") (pinfunction "1_1") (pintype "passive"))
      (node (ref "C3") (pin "1") (pinfunction "1_1") (pintype "passive"))
      (node (ref "C5") (pin "1") (pinfunction "1_1") (pintype "passive"))
      (node (ref "C7") (pin "1") (pinfunction "1_1") (pintype "passive"))
      (node (ref "CAP_COMP") (pin "5") (pinfunction "V+_5") (pintype "power_in"))
      (node (ref "CAP_SENSE_BUF") (pin "5") (pinfunction "V+_5") (pintype "power_in"))
      (node (ref "CLAMP1") (pin "C") (pinfunction "C_C") (pintype "passive"))
      (node (ref "DIS_SIG_Q") (pin "2") (pinfunction "S_2") (pintype "passive"))
      (node (ref "JP1") (pin "2") (pinfunction "2_2") (pintype "passive"))
      (node (ref "LOGIC_HEADER") (pin "5") (pinfunction "5_5") (pintype "passive"))
      (node (ref "LOGIC_HEADER") (pin "6") (pinfunction "6_6") (pintype "passive"))
      (node (ref "LOGIC_HEADER") (pin "7") (pinfunction "7_7") (pintype "passive"))
      (node (ref "MAN-DIS") (pin "B2") (pinfunction "2_B2") (pintype "passive"))
      (node (ref "R11") (pin "2") (pinfunction "2_2") (pintype "passive"))
      (node (ref "R29") (pin "1") (pinfunction "1_1") (pintype "passive"))
      (node (ref "R30") (pin "2") (pinfunction "2_2") (pintype "passive"))
      (node (ref "R6") (pin "1") (pinfunction "1_1") (pintype "passive"))
      (node (ref "R9") (pin "2") (pinfunction "2_2") (pintype "passive"))
      (node (ref "U2") (pin "21") (pinfunction "VCC_2_21") (pintype "power_in"))
      (node (ref "U2") (pin "52") (pinfunction "VCC_52") (pintype "power_in"))
    )
    (net (code "32") (name "12V") (class "Default")
      (node (ref "12V") (pin "P$1") (pinfunction "P$1_P$1") (pintype "bidirectional"))
      (node (ref "3.3REG") (pin "GATE") (pinfunction "IN_GATE") (pintype "input"))
      (node (ref "5.0REG") (pin "1") (pinfunction "IN_1") (pintype "input"))
      (node (ref "5.0REG") (pin "3") (pinfunction "EN_3") (pintype "input"))
      (node (ref "C16") (pin "1") (pinfunction "1_1") (pintype "passive"))
      (node (ref "C18") (pin "1") (pinfunction "1_1") (pintype "passive"))
      (node (ref "C20") (pin "1") (pinfunction "1_1") (pintype "passive"))
      (node (ref "C21") (pin "1") (pinfunction "1_1") (pintype "passive"))
      (node (ref "C23") (pin "1") (pinfunction "1_1") (pintype "passive"))
      (node (ref "CHARGE_U") (pin "P$1") (pinfunction "VT_P$1") (pintype "bidirectional"))
      (node (ref "CHARGE_U") (pin "P$4") (pinfunction "VCC_P$4") (pintype "bidirectional"))
      (node (ref "DRIB") (pin "1") (pinfunction "P$1_1") (pintype "bidirectional"))
      (node (ref "ON/OFF") (pin "IN2") (pinfunction "P2_IN2") (pintype "bidirectional"))
      (node (ref "OPTO_KICK") (pin "6") (pinfunction "COL_6") (pintype "passive"))
      (node (ref "OPTO_KICK") (pin "8") (pinfunction "COL_8") (pintype "passive"))
      (node (ref "POWER_HEADER") (pin "10") (pinfunction "10_10") (pintype "passive"))
      (node (ref "POWER_HEADER") (pin "6") (pinfunction "6_6") (pintype "passive"))
      (node (ref "POWER_HEADER") (pin "7") (pinfunction "7_7") (pintype "passive"))
      (node (ref "POWER_HEADER") (pin "8") (pinfunction "8_8") (pintype "passive"))
      (node (ref "POWER_HEADER") (pin "9") (pinfunction "9_9") (pintype "passive"))
      (node (ref "R10") (pin "2") (pinfunction "2_2") (pintype "passive"))
      (node (ref "U$1") (pin "P$4") (pinfunction "P$4_P$4") (pintype "bidirectional"))
      (node (ref "U$1") (pin "P$5") (pinfunction "P$5_P$5") (pintype "bidirectional"))
    )
    (net (code "33") (name "CAP+") (class "Default")
      (node (ref "C1") (pin "+") (pinfunction "+_+") (pintype "passive"))
      (node (ref "C2") (pin "+") (pinfunction "+_+") (pintype "passive"))
      (node (ref "CHARGE_D") (pin "C") (pinfunction "C_C") (pintype "passive"))
      (node (ref "CHIP") (pin "1") (pinfunction "P$1_1") (pintype "bidirectional"))
      (node (ref "CHIP_FLYBACK") (pin "CATHODE") (pinfunction "C_CATHODE") (pintype "passive"))
      (node (ref "DISCHARGE_D") (pin "A") (pinfunction "A_A") (pintype "passive"))
      (node (ref "KICK") (pin "1") (pinfunction "P$1_1") (pintype "bidirectional"))
      (node (ref "KICK_FLYBACK") (pin "CATHODE") (pinfunction "C_CATHODE") (pintype "passive"))
      (node (ref "R14") (pin "2") (pinfunction "2_2") (pintype "passive"))
      (node (ref "R24") (pin "2") (pinfunction "2_2") (pintype "passive"))
    )
    (net (code "34") (name "CHARGE") (class "Default")
      (node (ref "CHARGE_U") (pin "P$3") (pinfunction "CHRG_P$3") (pintype "bidirectional"))
      (node (ref "U2") (pin "51") (pinfunction "PA0_51") (pintype "bidirectional"))
    )
    (net (code "35") (name "Net-(5.0REG-BP)") (class "Default")
      (node (ref "5.0REG") (pin "4") (pinfunction "BP_4") (pintype "input"))
      (node (ref "C8") (pin "1") (pinfunction "1_1") (pintype "passive"))
    )
    (net (code "36") (name "Net-(ANDS-A1)") (class "Default")
      (node (ref "ANDS") (pin "P$1") (pinfunction "A1_P$1") (pintype "bidirectional"))
      (node (ref "ANDS") (pin "P$5") (pinfunction "A2_P$5") (pintype "bidirectional"))
      (node (ref "CAP_COMP") (pin "4") (pinfunction "OUT_4") (pintype "output"))
      (node (ref "R29") (pin "2") (pinfunction "2_2") (pintype "passive"))
      (node (ref "R7") (pin "1") (pinfunction "1_1") (pintype "passive"))
    )
    (net (code "37") (name "Net-(ANDS-Y1)") (class "Default")
      (node (ref "ANDS") (pin "P$7") (pinfunction "Y1_P$7") (pintype "bidirectional"))
      (node (ref "R25") (pin "2") (pinfunction "2_2") (pintype "passive"))
    )
    (net (code "38") (name "Net-(ANDS-Y2)") (class "Default")
      (node (ref "ANDS") (pin "P$3") (pinfunction "Y2_P$3") (pintype "bidirectional"))
      (node (ref "R26") (pin "2") (pinfunction "2_2") (pintype "passive"))
    )
    (net (code "39") (name "Net-(BB_CON-P$1)") (class "Default")
      (node (ref "BB_CON") (pin "1") (pinfunction "P$1_1") (pintype "bidirectional"))
      (node (ref "R6") (pin "2") (pinfunction "2_2") (pintype "passive"))
    )
    (net (code "40") (name "Net-(BB_CON-P$4)") (class "Default")
      (node (ref "BB_CON") (pin "4") (pinfunction "P$4_4") (pintype "bidirectional"))
      (node (ref "R5") (pin "2") (pinfunction "2_2") (pintype "passive"))
    )
    (net (code "41") (name "Net-(CAP_COMP-IN+)") (class "Default")
      (node (ref "CAP_COMP") (pin "1") (pinfunction "IN+_1") (pintype "input"))
      (node (ref "R7") (pin "2") (pinfunction "2_2") (pintype "passive"))
      (node (ref "R8") (pin "1") (pinfunction "1_1") (pintype "passive"))
    )
    (net (code "42") (name "Net-(CAP_COMP-IN-)") (class "Default")
      (node (ref "C6") (pin "1") (pinfunction "1_1") (pintype "passive"))
      (node (ref "CAP_COMP") (pin "3") (pinfunction "IN-_3") (pintype "input"))
      (node (ref "PWM_FILT") (pin "P$1") (pinfunction "P$1_P$1") (pintype "bidirectional"))
      (node (ref "R12") (pin "1") (pinfunction "1_1") (pintype "passive"))
    )
    (net (code "43") (name "Net-(CAP_SENSE_BUF-+IN)") (class "Default")
      (node (ref "CAP_SENSE_BUF") (pin "3") (pinfunction "+IN_3") (pintype "input"))
      (node (ref "CLAMP1") (pin "A") (pinfunction "A_A") (pintype "passive"))
      (node (ref "CLAMP2") (pin "C") (pinfunction "C_C") (pintype "passive"))
      (node (ref "R14") (pin "1") (pinfunction "1_1") (pintype "passive"))
      (node (ref "R15") (pin "2") (pinfunction "2_2") (pintype "passive"))
    )
    (net (code "44") (name "Net-(CHARGE_D-PadA)") (class "Default")
      (node (ref "CHARGE_D") (pin "A") (pinfunction "A_A") (pintype "passive"))
      (node (ref "U$1") (pin "P$1") (pinfunction "P$1_P$1") (pintype "bidirectional"))
    )
    (net (code "45") (name "Net-(CHARGE_U-GATE)") (class "Default")
      (node (ref "CHARGE_U") (pin "P$7") (pinfunction "GATE_P$7") (pintype "bidirectional"))
      (node (ref "SWITCH_Q") (pin "GATE") (pinfunction "G_GATE") (pintype "bidirectional"))
    )
    (net (code "46") (name "Net-(CHARGE_U-RBG)") (class "Default")
      (node (ref "C19") (pin "1") (pinfunction "1_1") (pintype "passive"))
      (node (ref "CHARGE_U") (pin "P$10") (pinfunction "RBG_P$10") (pintype "bidirectional"))
      (node (ref "RBG") (pin "2") (pinfunction "2_2") (pintype "passive"))
    )
    (net (code "47") (name "Net-(CHARGE_U-RDCM)") (class "Default")
      (node (ref "CHARGE_U") (pin "P$8") (pinfunction "RDCM_P$8") (pintype "bidirectional"))
      (node (ref "R31") (pin "1") (pinfunction "1_1") (pintype "passive"))
    )
    (net (code "48") (name "Net-(CHARGE_U-RV)") (class "Default")
      (node (ref "CHARGE_U") (pin "P$9") (pinfunction "RV_P$9") (pintype "bidirectional"))
      (node (ref "RVOUT") (pin "1") (pinfunction "1_1") (pintype "passive"))
    )
    (net (code "49") (name "Net-(CHARGE_U-SRC)") (class "Default")
      (node (ref "CHARGE_U") (pin "P$6") (pinfunction "SRC_P$6") (pintype "bidirectional"))
      (node (ref "RSENSE") (pin "2") (pinfunction "2_2") (pintype "passive"))
      (node (ref "SWITCH_Q") (pin "SOURCE") (pinfunction "S_SOURCE") (pintype "bidirectional"))
    )
    (net (code "50") (name "Net-(CHIP-P$2)") (class "Default")
      (node (ref "CHIP") (pin "2") (pinfunction "P$2_2") (pintype "bidirectional"))
      (node (ref "CHIP_FLYBACK") (pin "ANODE") (pinfunction "A_ANODE") (pintype "passive"))
      (node (ref "CHIP_Q") (pin "DRAIN") (pinfunction "D_DRAIN") (pintype "bidirectional"))
    )
    (net (code "51") (name "Net-(CHIP_Q-G)") (class "Default")
      (node (ref "CHIP_Q") (pin "GATE") (pinfunction "G_GATE") (pintype "bidirectional"))
      (node (ref "OPTO_KICK") (pin "7") (pinfunction "EMIT_7") (pintype "passive"))
      (node (ref "R28") (pin "1") (pinfunction "1_1") (pintype "passive"))
    )
    (net (code "52") (name "Net-(DISCHARGE_Q-D)") (class "Default")
      (node (ref "DISCHARGE_Q") (pin "DRAIN") (pinfunction "D_DRAIN") (pintype "bidirectional"))
      (node (ref "R1") (pin "P$1") (pinfunction "1_P$1") (pintype "passive"))
    )
    (net (code "53") (name "Net-(DISCHARGE_Q-G)") (class "Default")
      (node (ref "DIS") (pin "P$1") (pinfunction "P$1_P$1") (pintype "bidirectional"))
      (node (ref "DISCHARGE_Q") (pin "GATE") (pinfunction "G_GATE") (pintype "bidirectional"))
      (node (ref "DIS_SIG_Q") (pin "3") (pinfunction "D_3") (pintype "passive"))
      (node (ref "MAN-DIS") (pin "A2") (pinfunction "1_A2") (pintype "passive"))
      (node (ref "R35") (pin "2") (pinfunction "2_2") (pintype "passive"))
    )
    (net (code "54") (name "Net-(DRIB-P$2)") (class "Default")
      (node (ref "DRIB") (pin "2") (pinfunction "P$2_2") (pintype "bidirectional"))
      (node (ref "DRIB_TRAN") (pin "DRAIN") (pinfunction "D_DRAIN") (pintype "bidirectional"))
    )
    (net (code "55") (name "Net-(KICK-P$2)") (class "Default")
      (node (ref "KICK") (pin "2") (pinfunction "P$2_2") (pintype "bidirectional"))
      (node (ref "KICK_FLYBACK") (pin "ANODE") (pinfunction "A_ANODE") (pintype "passive"))
      (node (ref "KICK_Q") (pin "DRAIN") (pinfunction "D_DRAIN") (pintype "bidirectional"))
    )
    (net (code "56") (name "Net-(KICK_Q-G)") (class "Default")
      (node (ref "KICK_Q") (pin "GATE") (pinfunction "G_GATE") (pintype "bidirectional"))
      (node (ref "OPTO_KICK") (pin "5") (pinfunction "EMIT_5") (pintype "passive"))
      (node (ref "R27") (pin "1") (pinfunction "1_1") (pintype "passive"))
    )
    (net (code "57") (name "Net-(LED2-PadA)") (class "Default")
      (node (ref "LED2") (pin "A") (pinfunction "A_A") (pintype "passive"))
      (node (ref "R17") (pin "1") (pinfunction "1_1") (pintype "passive"))
    )
    (net (code "58") (name "Net-(LED3-PadA)") (class "Default")
      (node (ref "LED3") (pin "A") (pinfunction "A_A") (pintype "passive"))
      (node (ref "R18") (pin "1") (pinfunction "1_1") (pintype "passive"))
    )
    (net (code "59") (name "Net-(LED4-PadA)") (class "Default")
      (node (ref "LED4") (pin "A") (pinfunction "A_A") (pintype "passive"))
      (node (ref "R19") (pin "1") (pinfunction "1_1") (pintype "passive"))
    )
    (net (code "60") (name "Net-(LED5-PadA)") (class "Default")
      (node (ref "LED5") (pin "A") (pinfunction "A_A") (pintype "passive"))
      (node (ref "R20") (pin "1") (pinfunction "1_1") (pintype "passive"))
    )
    (net (code "61") (name "Net-(LED6-PadA)") (class "Default")
      (node (ref "LED6") (pin "A") (pinfunction "A_A") (pintype "passive"))
      (node (ref "R21") (pin "1") (pinfunction "1_1") (pintype "passive"))
    )
    (net (code "62") (name "Net-(LED7-PadA)") (class "Default")
      (node (ref "LED7") (pin "A") (pinfunction "A_A") (pintype "passive"))
      (node (ref "R22") (pin "1") (pinfunction "1_1") (pintype "passive"))
    )
    (net (code "63") (name "Net-(NEON-Pad1)") (class "Default")
      (node (ref "NEON") (pin "1") (pinfunction "1_1") (pintype "passive"))
      (node (ref "R24") (pin "1") (pinfunction "1_1") (pintype "passive"))
    )
    (net (code "64") (name "Net-(OPTO_KICKA-A)") (class "Default")
      (node (ref "OPTO_KICK") (pin "1") (pinfunction "A_1") (pintype "passive"))
      (node (ref "R26") (pin "1") (pinfunction "1_1") (pintype "passive"))
    )
    (net (code "65") (name "Net-(OPTO_KICKB-A)") (class "Default")
      (node (ref "OPTO_KICK") (pin "3") (pinfunction "A_3") (pintype "passive"))
      (node (ref "R25") (pin "1") (pinfunction "1_1") (pintype "passive"))
    )
    (net (code "66") (name "Net-(R1-2)") (class "Default")
      (node (ref "DISCHARGE_D") (pin "C") (pinfunction "C_C") (pintype "passive"))
      (node (ref "R1") (pin "P$2") (pinfunction "2_P$2") (pintype "passive"))
    )
    (net (code "67") (name "Net-(R2-Pad2)") (class "Default")
      (node (ref "R2") (pin "2") (pinfunction "2_2") (pintype "passive"))
      (node (ref "SPI_HEADER") (pin "1") (pinfunction "1_1") (pintype "passive"))
    )
    (net (code "68") (name "Net-(R3-Pad2)") (class "Default")
      (node (ref "R3") (pin "2") (pinfunction "2_2") (pintype "passive"))
      (node (ref "SPI_HEADER") (pin "2") (pinfunction "2_2") (pintype "passive"))
    )
    (net (code "69") (name "Net-(R4-Pad2)") (class "Default")
      (node (ref "R4") (pin "2") (pinfunction "2_2") (pintype "passive"))
      (node (ref "SPI_HEADER") (pin "3") (pinfunction "3_3") (pintype "passive"))
    )
    (net (code "70") (name "Net-(SWITCH_Q-D)") (class "Default")
      (node (ref "R31") (pin "2") (pinfunction "2_2") (pintype "passive"))
      (node (ref "RVOUT") (pin "2") (pinfunction "2_2") (pintype "passive"))
      (node (ref "SWITCH_Q") (pin "DRAIN") (pinfunction "D_DRAIN") (pintype "bidirectional"))
      (node (ref "U$1") (pin "P$6") (pinfunction "P$6_P$6") (pintype "bidirectional"))
      (node (ref "U$1") (pin "P$7") (pinfunction "P$7_P$7") (pintype "bidirectional"))
    )
    (net (code "71") (name "Net-(U2-AREF)") (class "Default")
      (node (ref "C4") (pin "2") (pinfunction "2_2") (pintype "passive"))
      (node (ref "U2") (pin "62") (pinfunction "AREF_62") (pintype "input"))
    )
    (net (code "72") (name "Net-(U2-AVCC)") (class "Default")
      (node (ref "C12") (pin "2") (pinfunction "2_2") (pintype "passive"))
      (node (ref "R30") (pin "1") (pinfunction "1_1") (pintype "passive"))
      (node (ref "U2") (pin "64") (pinfunction "AVCC_64") (pintype "power_in"))
    )
    (net (code "73") (name "unconnected-(JP1-Pad3)") (class "Default")
      (node (ref "JP1") (pin "3") (pinfunction "3_3") (pintype "passive"))
    )
    (net (code "74") (name "unconnected-(SPARE_HEADER-Pad1)") (class "Default")
      (node (ref "SPARE_HEADER") (pin "1") (pinfunction "1_1") (pintype "passive"))
    )
    (net (code "75") (name "unconnected-(SPARE_HEADER-Pad2)") (class "Default")
      (node (ref "SPARE_HEADER") (pin "2") (pinfunction "2_2") (pintype "passive"))
    )
    (net (code "76") (name "unconnected-(SPARE_HEADER-Pad3)") (class "Default")
      (node (ref "SPARE_HEADER") (pin "3") (pinfunction "3_3") (pintype "passive"))
    )
    (net (code "77") (name "unconnected-(SPARE_HEADER-Pad4)") (class "Default")
      (node (ref "SPARE_HEADER") (pin "4") (pinfunction "4_4") (pintype "passive"))
    )
    (net (code "78") (name "unconnected-(SPARE_HEADER-Pad5)") (class "Default")
      (node (ref "SPARE_HEADER") (pin "5") (pinfunction "5_5") (pintype "passive"))
    )
    (net (code "79") (name "unconnected-(SPARE_HEADER-Pad6)") (class "Default")
      (node (ref "SPARE_HEADER") (pin "6") (pinfunction "6_6") (pintype "passive"))
    )
    (net (code "80") (name "unconnected-(SPARE_HEADER-Pad7)") (class "Default")
      (node (ref "SPARE_HEADER") (pin "7") (pinfunction "7_7") (pintype "passive"))
    )
    (net (code "81") (name "unconnected-(SPARE_HEADER-Pad8)") (class "Default")
      (node (ref "SPARE_HEADER") (pin "8") (pinfunction "8_8") (pintype "passive"))
    )
    (net (code "82") (name "unconnected-(SPARE_HEADER-Pad9)") (class "Default")
      (node (ref "SPARE_HEADER") (pin "9") (pinfunction "9_9") (pintype "passive"))
    )
    (net (code "83") (name "unconnected-(SPARE_HEADER-Pad10)") (class "Default")
      (node (ref "SPARE_HEADER") (pin "10") (pinfunction "10_10") (pintype "passive"))
    )
    (net (code "84") (name "unconnected-(SPI_HEADER-Pad9)") (class "Default")
      (node (ref "SPI_HEADER") (pin "9") (pinfunction "9_9") (pintype "passive"))
    )
    (net (code "85") (name "unconnected-(SPI_HEADER-Pad10)") (class "Default")
      (node (ref "SPI_HEADER") (pin "10") (pinfunction "10_10") (pintype "passive"))
    )
    (net (code "86") (name "unconnected-(U2-(TOSC1)_XTAL1-Pad24)") (class "Default")
      (node (ref "U2") (pin "24") (pinfunction "(TOSC1)_XTAL1_24") (pintype "input"))
    )
    (net (code "87") (name "unconnected-(U2-(TOSC2)_XTAL2-Pad23)") (class "Default")
      (node (ref "U2") (pin "23") (pinfunction "(TOSC2)_XTAL2_23") (pintype "output"))
    )
    (net (code "88") (name "unconnected-(U2-DNC-Pad1)") (class "Default")
      (node (ref "U2") (pin "1") (pinfunction "DNC_1") (pintype "no_connect"))
    )
    (net (code "89") (name "unconnected-(U2-PA2-Pad49)") (class "Default")
      (node (ref "U2") (pin "49") (pinfunction "PA2_49") (pintype "bidirectional"))
    )
    (net (code "90") (name "unconnected-(U2-PA6-Pad45)") (class "Default")
      (node (ref "U2") (pin "45") (pinfunction "PA6_45") (pintype "bidirectional"))
    )
    (net (code "91") (name "unconnected-(U2-PA7-Pad44)") (class "Default")
      (node (ref "U2") (pin "44") (pinfunction "PA7_44") (pintype "bidirectional"))
    )
    (net (code "92") (name "unconnected-(U2-PB4-Pad14)") (class "Default")
      (node (ref "U2") (pin "14") (pinfunction "PB4_14") (pintype "bidirectional"))
    )
    (net (code "93") (name "unconnected-(U2-PC0-Pad35)") (class "Default")
      (node (ref "U2") (pin "35") (pinfunction "PC0_35") (pintype "bidirectional"))
    )
    (net (code "94") (name "unconnected-(U2-PC7-Pad42)") (class "Default")
      (node (ref "U2") (pin "42") (pinfunction "PC7_42") (pintype "bidirectional"))
    )
    (net (code "95") (name "unconnected-(U2-PD0-Pad25)") (class "Default")
      (node (ref "U2") (pin "25") (pinfunction "PD0_25") (pintype "bidirectional"))
    )
    (net (code "96") (name "unconnected-(U2-PD1-Pad26)") (class "Default")
      (node (ref "U2") (pin "26") (pinfunction "PD1_26") (pintype "bidirectional"))
    )
    (net (code "97") (name "unconnected-(U2-PD2-Pad27)") (class "Default")
      (node (ref "U2") (pin "27") (pinfunction "PD2_27") (pintype "bidirectional"))
    )
    (net (code "98") (name "unconnected-(U2-PD3-Pad28)") (class "Default")
      (node (ref "U2") (pin "28") (pinfunction "PD3_28") (pintype "bidirectional"))
    )
    (net (code "99") (name "unconnected-(U2-PD4-Pad29)") (class "Default")
      (node (ref "U2") (pin "29") (pinfunction "PD4_29") (pintype "bidirectional"))
    )
    (net (code "100") (name "unconnected-(U2-PD5-Pad30)") (class "Default")
      (node (ref "U2") (pin "30") (pinfunction "PD5_30") (pintype "bidirectional"))
    )
    (net (code "101") (name "unconnected-(U2-PD6-Pad31)") (class "Default")
      (node (ref "U2") (pin "31") (pinfunction "PD6_31") (pintype "bidirectional"))
    )
    (net (code "102") (name "unconnected-(U2-PD7-Pad32)") (class "Default")
      (node (ref "U2") (pin "32") (pinfunction "PD7_32") (pintype "bidirectional"))
    )
    (net (code "103") (name "unconnected-(U2-PE0-Pad2)") (class "Default")
      (node (ref "U2") (pin "2") (pinfunction "PE0_2") (pintype "bidirectional"))
    )
    (net (code "104") (name "unconnected-(U2-PE1-Pad3)") (class "Default")
      (node (ref "U2") (pin "3") (pinfunction "PE1_3") (pintype "bidirectional"))
    )
    (net (code "105") (name "unconnected-(U2-PE2-Pad4)") (class "Default")
      (node (ref "U2") (pin "4") (pinfunction "PE2_4") (pintype "bidirectional"))
    )
    (net (code "106") (name "unconnected-(U2-PE3-Pad5)") (class "Default")
      (node (ref "U2") (pin "5") (pinfunction "PE3_5") (pintype "bidirectional"))
    )
    (net (code "107") (name "unconnected-(U2-PE4-Pad6)") (class "Default")
      (node (ref "U2") (pin "6") (pinfunction "PE4_6") (pintype "bidirectional"))
    )
    (net (code "108") (name "unconnected-(U2-PE5-Pad7)") (class "Default")
      (node (ref "U2") (pin "7") (pinfunction "PE5_7") (pintype "bidirectional"))
    )
    (net (code "109") (name "unconnected-(U2-PE6-Pad8)") (class "Default")
      (node (ref "U2") (pin "8") (pinfunction "PE6_8") (pintype "bidirectional"))
    )
    (net (code "110") (name "unconnected-(U2-PE7-Pad9)") (class "Default")
      (node (ref "U2") (pin "9") (pinfunction "PE7_9") (pintype "bidirectional"))
    )
    (net (code "111") (name "unconnected-(U2-PF3-Pad58)") (class "Default")
      (node (ref "U2") (pin "58") (pinfunction "PF3_58") (pintype "bidirectional"))
    )
    (net (code "112") (name "unconnected-(U2-PF4-Pad57)") (class "Default")
      (node (ref "U2") (pin "57") (pinfunction "PF4_57") (pintype "bidirectional"))
    )
    (net (code "113") (name "unconnected-(U2-PF5-Pad56)") (class "Default")
      (node (ref "U2") (pin "56") (pinfunction "PF5_56") (pintype "bidirectional"))
    )
    (net (code "114") (name "unconnected-(U2-PF6-Pad55)") (class "Default")
      (node (ref "U2") (pin "55") (pinfunction "PF6_55") (pintype "bidirectional"))
    )
    (net (code "115") (name "unconnected-(U2-PF7-Pad54)") (class "Default")
      (node (ref "U2") (pin "54") (pinfunction "PF7_54") (pintype "bidirectional"))
    )
    (net (code "116") (name "unconnected-(U2-PG0-Pad33)") (class "Default")
      (node (ref "U2") (pin "33") (pinfunction "PG0_33") (pintype "bidirectional"))
    )
    (net (code "117") (name "unconnected-(U2-PG1-Pad34)") (class "Default")
      (node (ref "U2") (pin "34") (pinfunction "PG1_34") (pintype "bidirectional"))
    )
    (net (code "118") (name "unconnected-(U2-PG2-Pad43)") (class "Default")
      (node (ref "U2") (pin "43") (pinfunction "PG2_43") (pintype "bidirectional"))
    )
    (net (code "119") (name "unconnected-(U2-PG3-Pad18)") (class "Default")
      (node (ref "U2") (pin "18") (pinfunction "PG3_18") (pintype "bidirectional"))
    )
    (net (code "120") (name "unconnected-(U2-PG4-Pad19)") (class "Default")
      (node (ref "U2") (pin "19") (pinfunction "PG4_19") (pintype "bidirectional"))
    )
  )
)
